# top_sheet.net
KiCad netlist of a schematic drawn in Altium Designer
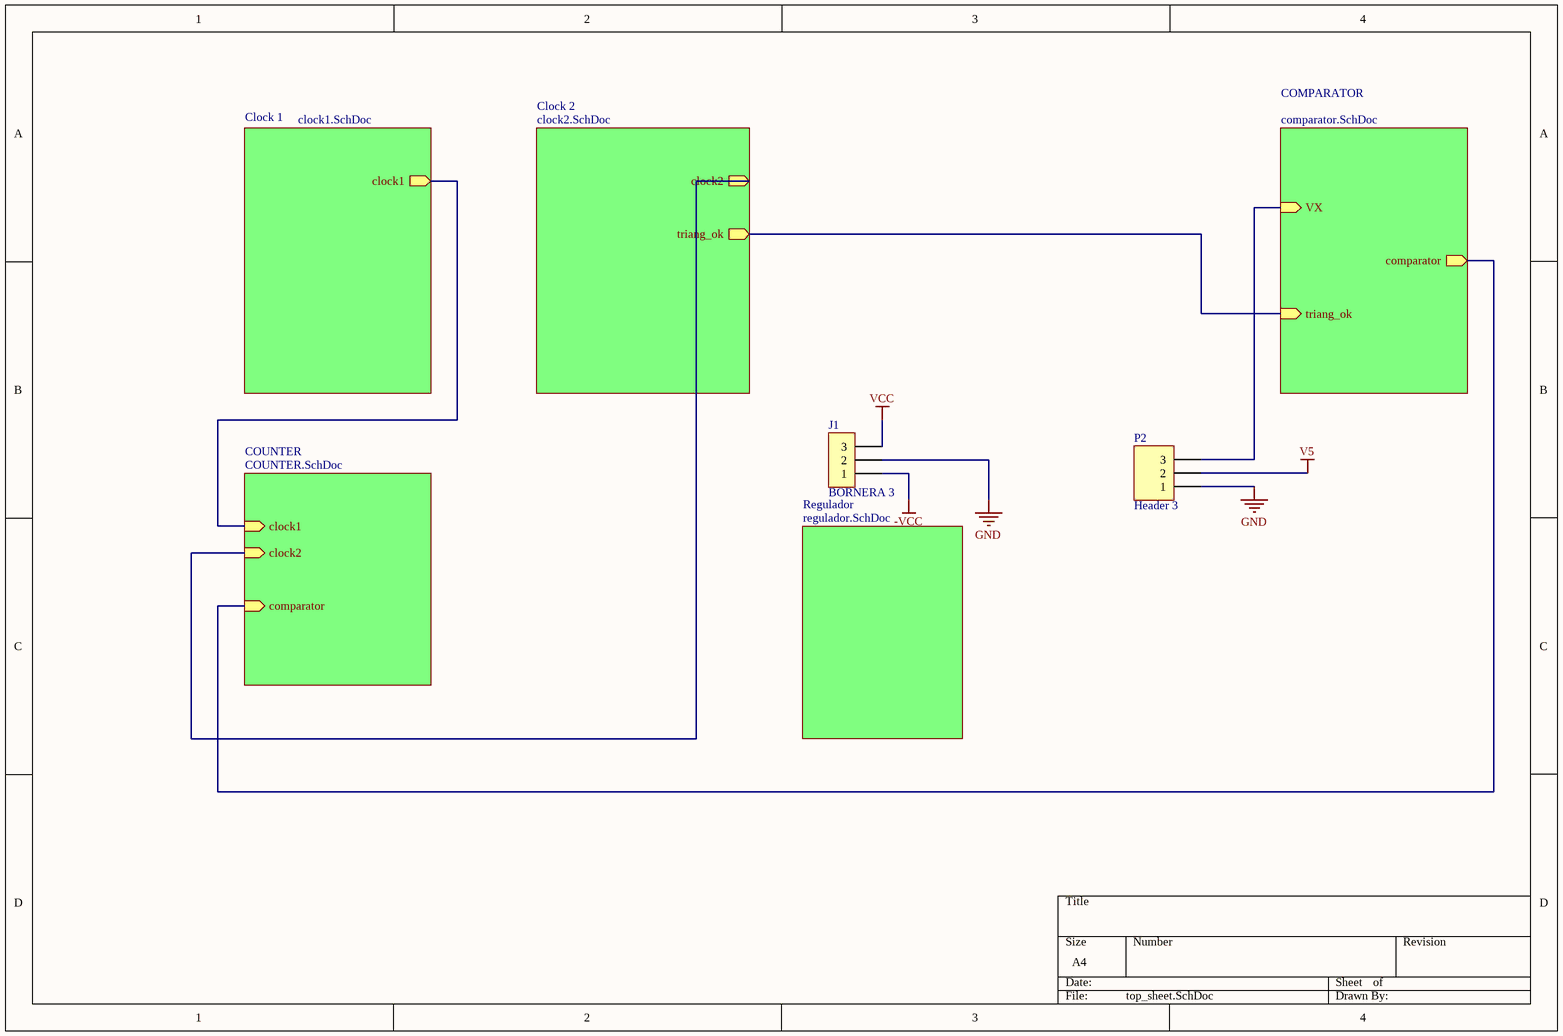
[diagram p0: top_sheet.SchDoc]

(export (version "E")
  (design (tool "Eeschema 10.0.6"))
  (components
    (comp (ref "J1")
      (value "BORNERA 3")
      (footprint "BORNERA3")
      (libsource (lib "LIBEBAL") (part "BORNERA 3"))
    )
    (comp (ref "P2")
      (value "Header 3")
      (footprint "HDR1X3")
      (description "Header, 3-Pin")
      (fields (field (name "PUBLISHER") "Altium Limited"))
      (libsource (lib "Miscellaneous Connectors") (part "Header 3"))
    )
  )
  (nets
    (net (code "1") (name "-VCC") (class "Default")
      (node (ref "J1") (pin "1") (pinfunction "1_1") (pintype "passive"))
    )
    (net (code "2") (name "/VX") (class "Default")
      (node (ref "P2") (pin "3") (pinfunction "3_3") (pintype "passive"))
    )
    (net (code "7") (name "GND") (class "Default")
      (node (ref "J1") (pin "2") (pinfunction "2_2") (pintype "passive"))
      (node (ref "P2") (pin "1") (pinfunction "1_1") (pintype "passive"))
    )
    (net (code "8") (name "V5") (class "Default")
      (node (ref "P2") (pin "2") (pinfunction "2_2") (pintype "passive"))
    )
    (net (code "9") (name "VCC") (class "Default")
      (node (ref "J1") (pin "3") (pinfunction "3_3") (pintype "passive"))
    )
  )
)
